# USB_TTL.net
KiCad netlist of a schematic drawn in Altium Designer
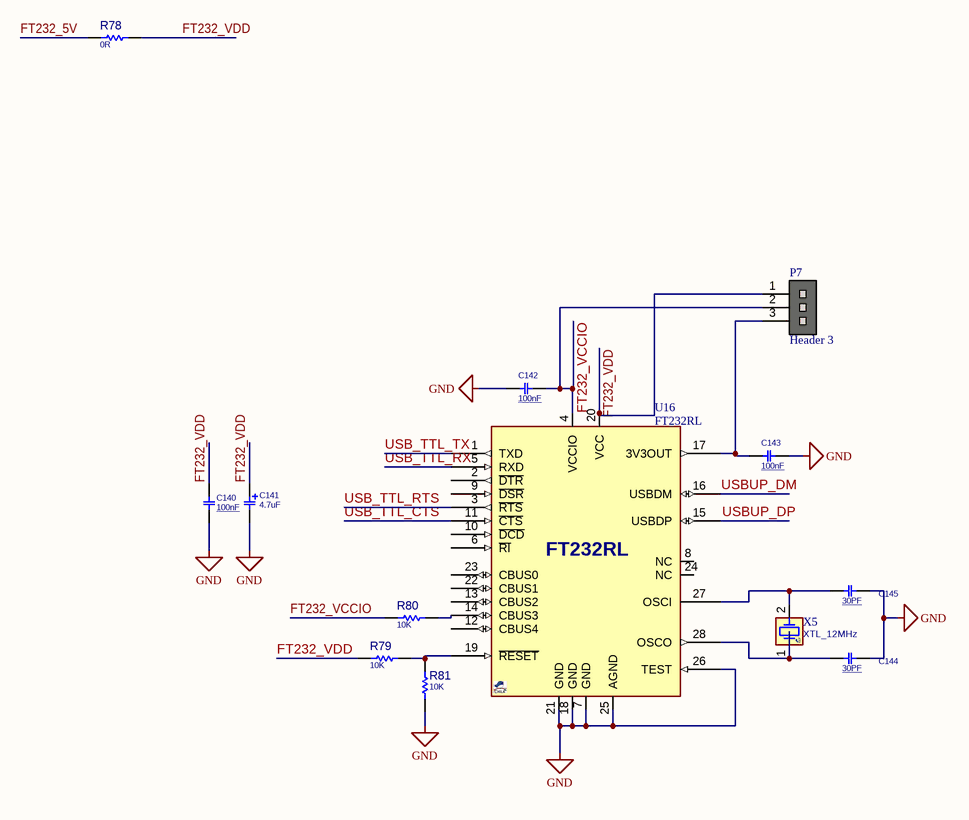
[diagram p0: USB_TTL.SchDoc]

(export (version "E")
  (design (tool "Eeschema 10.0.6"))
  (components
    (comp (ref "C140")
      (value "100nF")
      (footprint "0603")
      (description "CAP, FILM, 1uF, 16V, Acryl, 20%, 1210")
      (fields (field (name "MANF_P#") "ECP-U1C105MA5") (field (name "MANF") "Panasonic"))
      (libsource (lib "cap_film_smd_passive") (part "CAP_SMD_FILM_1u16v_1210"))
    )
    (comp (ref "C141")
      (value "4.7uF")
      (footprint "C_TN_3216")
      (description "CAP, SMD, TAN")
      (fields (field (name "MANF") "VISHAY") (field (name "MANF_P#") "T55A106M6R3C0300"))
      (libsource (lib "CapTantal_passive") (part "CAP_SMD_TAN_10uF_6.3V"))
    )
    (comp (ref "C142")
      (value "100nF")
      (footprint "0603")
      (description "CAP, FILM, 1uF, 16V, Acryl, 20%, 1210")
      (fields (field (name "MANF_P#") "ECP-U1C105MA5") (field (name "MANF") "Panasonic"))
      (libsource (lib "cap_film_smd_passive") (part "CAP_SMD_FILM_1u16v_1210"))
    )
    (comp (ref "C143")
      (value "100nF")
      (footprint "0603")
      (description "CAP, FILM, 1uF, 16V, Acryl, 20%, 1210")
      (fields (field (name "MANF_P#") "ECP-U1C105MA5") (field (name "MANF") "Panasonic"))
      (libsource (lib "cap_film_smd_passive") (part "CAP_SMD_FILM_1u16v_1210"))
    )
    (comp (ref "C144")
      (value "30PF")
      (footprint "C0805")
      (description "CAP, MLCC, 1nF, 50V, C0G, 10%, 0402")
      (fields (field (name "MANF") "Murata"))
      (libsource (lib "mlcc_smd_passive") (part "CAP_SMD_MLCC"))
    )
    (comp (ref "C145")
      (value "30PF")
      (footprint "C0805")
      (description "CAP, MLCC, 1nF, 50V, C0G, 10%, 0402")
      (fields (field (name "MANF") "Murata"))
      (libsource (lib "mlcc_smd_passive") (part "CAP_SMD_MLCC"))
    )
    (comp (ref "P7")
      (value "Header 3")
      (footprint "HDR 1X3")
      (description "Header, 3-Pin")
      (libsource (lib "Header") (part "Header 3"))
    )
    (comp (ref "R78")
      (value "0R")
      (footprint "R0603")
      (description "RESISTOR, SMD")
      (libsource (lib "passive_smd") (part "RES_SMD_0603"))
    )
    (comp (ref "R79")
      (value "10K")
      (footprint "R0603")
      (description "RESISTOR, SMD")
      (libsource (lib "passive_smd") (part "RES_SMD_0603"))
    )
    (comp (ref "R80")
      (value "10K")
      (footprint "R0603")
      (description "RESISTOR, SMD")
      (libsource (lib "passive_smd") (part "RES_SMD_0603"))
    )
    (comp (ref "R81")
      (value "10K")
      (footprint "R0603")
      (description "RESISTOR, SMD")
      (libsource (lib "passive_smd") (part "RES_SMD_0603"))
    )
    (comp (ref "U16")
      (value "FT232RL")
      (footprint "SOG65_28_W")
      (description "USB-UART, Asynchronous Serial Data Transfer Chip, SSOP-28")
      (fields (field (name "MANF") "FTDI"))
      (libsource (lib "usbic") (part "FT232RL_SSOP28"))
    )
    (comp (ref "X5")
      (value "XTL_12MHz")
      (footprint "XTL_2_11X5")
      (description "Crystal MOST POPULAR ABL HC49 PACKAGE")
      (fields (field (name "MANF") "ABRACON") (field (name "MANF_P#") "ABLS-8.000MHZ-B4-T"))
      (libsource (lib "crystal") (part "XTL_2_HC49_8MHz_SMD"))
    )
  )
  (nets
    (net (code "1") (name "/FT232_5V") (class "Default")
      (node (ref "R78") (pin "1") (pinfunction "1_1") (pintype "passive"))
    )
    (net (code "2") (name "/FT232_VCCIO") (class "Default")
      (node (ref "C142") (pin "2") (pinfunction "2_2") (pintype "passive"))
      (node (ref "P7") (pin "2") (pinfunction "2_2") (pintype "passive"))
      (node (ref "R80") (pin "2") (pinfunction "2_2") (pintype "passive"))
      (node (ref "U16") (pin "4") (pinfunction "VCCIO_4") (pintype "power_in"))
    )
    (net (code "3") (name "/FT232_VDD") (class "Default")
      (node (ref "C140") (pin "1") (pinfunction "1_1") (pintype "passive"))
      (node (ref "C141") (pin "1") (pinfunction "1_1") (pintype "passive"))
      (node (ref "P7") (pin "1") (pinfunction "1_1") (pintype "passive"))
      (node (ref "R78") (pin "2") (pinfunction "2_2") (pintype "passive"))
      (node (ref "R79") (pin "1") (pinfunction "1_1") (pintype "passive"))
      (node (ref "U16") (pin "20") (pinfunction "VCC_20") (pintype "power_in"))
    )
    (net (code "4") (name "/USBUP_DM") (class "Default")
      (node (ref "U16") (pin "16") (pinfunction "USBDM_16") (pintype "bidirectional"))
    )
    (net (code "5") (name "/USBUP_DP") (class "Default")
      (node (ref "U16") (pin "15") (pinfunction "USBDP_15") (pintype "bidirectional"))
    )
    (net (code "6") (name "/USB_TTL_CTS") (class "Default")
      (node (ref "U16") (pin "11") (pinfunction "~{CTS}_11") (pintype "input"))
    )
    (net (code "7") (name "/USB_TTL_RTS") (class "Default")
      (node (ref "U16") (pin "3") (pinfunction "~{RTS}_3") (pintype "output"))
    )
    (net (code "8") (name "/USB_TTL_RX") (class "Default")
      (node (ref "U16") (pin "5") (pinfunction "RXD_5") (pintype "input"))
    )
    (net (code "9") (name "/USB_TTL_TX") (class "Default")
      (node (ref "U16") (pin "1") (pinfunction "TXD_1") (pintype "output"))
    )
    (net (code "10") (name "GND") (class "Default")
      (node (ref "C140") (pin "2") (pinfunction "2_2") (pintype "passive"))
      (node (ref "C141") (pin "2") (pinfunction "2_2") (pintype "passive"))
      (node (ref "C142") (pin "1") (pinfunction "1_1") (pintype "passive"))
      (node (ref "C143") (pin "2") (pinfunction "2_2") (pintype "passive"))
      (node (ref "C144") (pin "2") (pinfunction "2_2") (pintype "passive"))
      (node (ref "C145") (pin "2") (pinfunction "2_2") (pintype "passive"))
      (node (ref "R81") (pin "2") (pinfunction "2_2") (pintype "passive"))
      (node (ref "U16") (pin "18") (pinfunction "GND_18") (pintype "power_in"))
      (node (ref "U16") (pin "21") (pinfunction "GND_21") (pintype "power_in"))
      (node (ref "U16") (pin "25") (pinfunction "AGND_25") (pintype "power_in"))
      (node (ref "U16") (pin "26") (pinfunction "TEST_26") (pintype "input"))
      (node (ref "U16") (pin "7") (pinfunction "GND_7") (pintype "power_in"))
    )
    (net (code "11") (name "Net-(U16-3V3OUT)") (class "Default")
      (node (ref "C143") (pin "1") (pinfunction "1_1") (pintype "passive"))
      (node (ref "P7") (pin "3") (pinfunction "3_3") (pintype "passive"))
      (node (ref "U16") (pin "17") (pinfunction "3V3OUT_17") (pintype "output"))
    )
    (net (code "12") (name "Net-(U16-CBUS3)") (class "Default")
      (node (ref "R80") (pin "1") (pinfunction "1_1") (pintype "passive"))
      (node (ref "U16") (pin "14") (pinfunction "CBUS3_14") (pintype "bidirectional"))
    )
    (net (code "13") (name "Net-(U16-OSCI)") (class "Default")
      (node (ref "C145") (pin "1") (pinfunction "1_1") (pintype "passive"))
      (node (ref "U16") (pin "27") (pinfunction "OSCI_27") (pintype "passive"))
      (node (ref "X5") (pin "2") (pinfunction "OSC2_2") (pintype "passive"))
    )
    (net (code "14") (name "Net-(U16-OSCO)") (class "Default")
      (node (ref "C144") (pin "1") (pinfunction "1_1") (pintype "passive"))
      (node (ref "U16") (pin "28") (pinfunction "OSCO_28") (pintype "output"))
      (node (ref "X5") (pin "1") (pinfunction "OSC1_1") (pintype "passive"))
    )
    (net (code "15") (name "Net-(U16-~{RESET})") (class "Default")
      (node (ref "R79") (pin "2") (pinfunction "2_2") (pintype "passive"))
      (node (ref "R81") (pin "1") (pinfunction "1_1") (pintype "passive"))
      (node (ref "U16") (pin "19") (pinfunction "~{RESET}_19") (pintype "input"))
    )
    (net (code "16") (name "unconnected-(U16-CBUS0-Pad23)") (class "Default")
      (node (ref "U16") (pin "23") (pinfunction "CBUS0_23") (pintype "bidirectional"))
    )
    (net (code "17") (name "unconnected-(U16-CBUS1-Pad22)") (class "Default")
      (node (ref "U16") (pin "22") (pinfunction "CBUS1_22") (pintype "bidirectional"))
    )
    (net (code "18") (name "unconnected-(U16-CBUS2-Pad13)") (class "Default")
      (node (ref "U16") (pin "13") (pinfunction "CBUS2_13") (pintype "bidirectional"))
    )
    (net (code "19") (name "unconnected-(U16-CBUS4-Pad12)") (class "Default")
      (node (ref "U16") (pin "12") (pinfunction "CBUS4_12") (pintype "bidirectional"))
    )
    (net (code "20") (name "unconnected-(U16-NC-Pad8)") (class "Default")
      (node (ref "U16") (pin "8") (pinfunction "NC_8") (pintype "passive"))
    )
    (net (code "21") (name "unconnected-(U16-NC-Pad24)") (class "Default")
      (node (ref "U16") (pin "24") (pinfunction "NC_24") (pintype "passive"))
    )
    (net (code "22") (name "unconnected-(U16-~{DCD}-Pad10)") (class "Default")
      (node (ref "U16") (pin "10") (pinfunction "~{DCD}_10") (pintype "input"))
    )
    (net (code "23") (name "unconnected-(U16-~{DSR}-Pad9)") (class "Default")
      (node (ref "U16") (pin "9") (pinfunction "~{DSR}_9") (pintype "input"))
    )
    (net (code "24") (name "unconnected-(U16-~{DTR}-Pad2)") (class "Default")
      (node (ref "U16") (pin "2") (pinfunction "~{DTR}_2") (pintype "output"))
    )
    (net (code "25") (name "unconnected-(U16-~{RI}-Pad6)") (class "Default")
      (node (ref "U16") (pin "6") (pinfunction "~{RI}_6") (pintype "input"))
    )
  )
)
